# DC_Offset.net
KiCad netlist of a schematic drawn in EAGLE
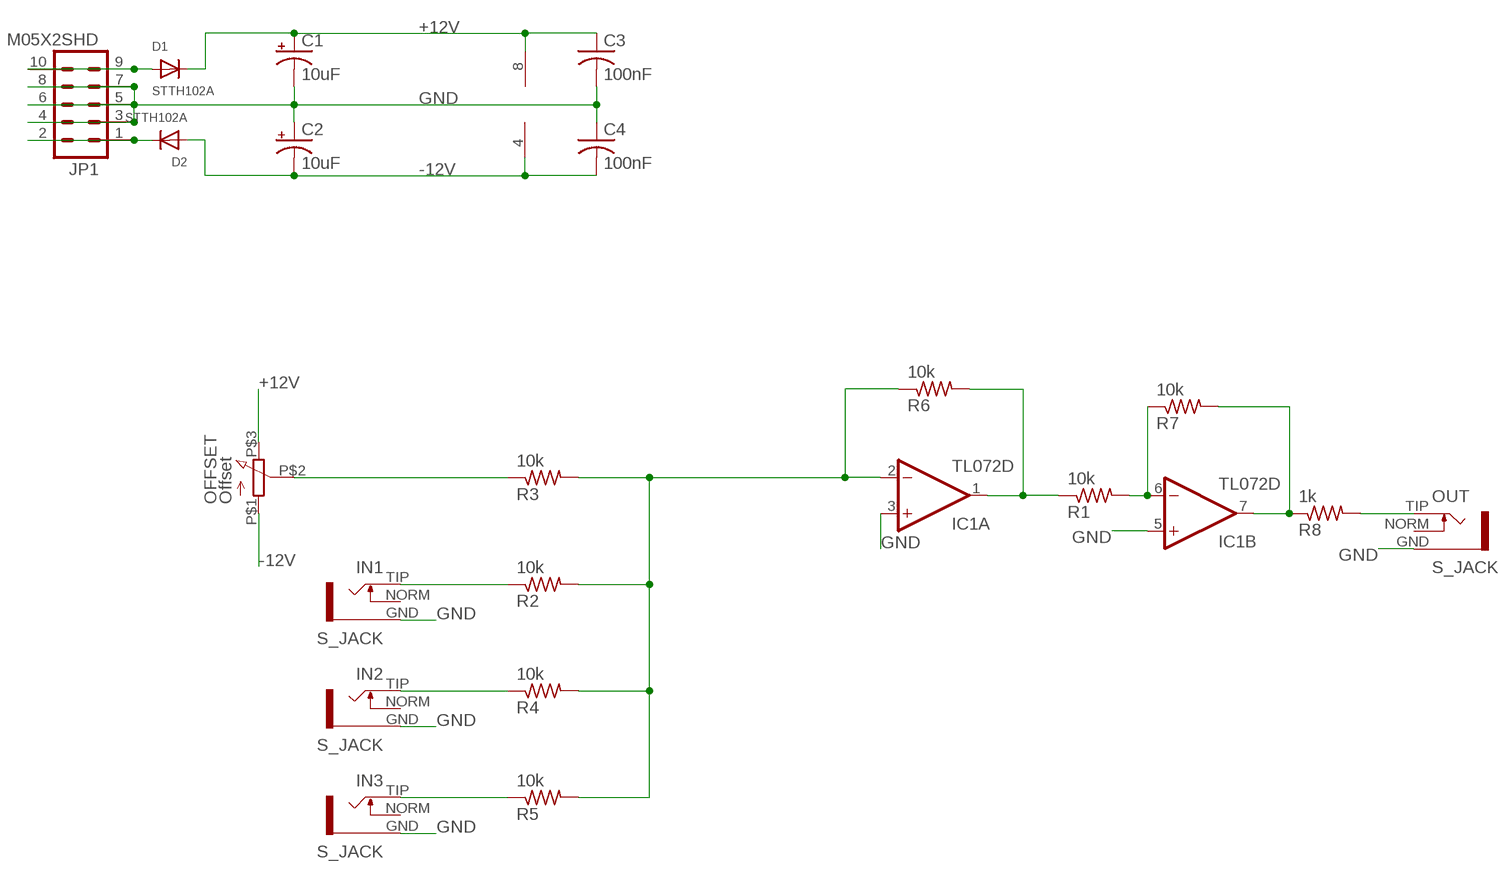
[diagram p0: schematic, sheet 1]

(export (version "E")
  (design (tool "Eeschema 10.0.6"))
  (components
    (comp (ref "C1")
      (value "10uF")
      (footprint "eagle-import:153CLV-0505")
      (libsource (lib "eagle-import") (part "CPOL-US153CLV-0505"))
    )
    (comp (ref "C2")
      (value "10uF")
      (footprint "eagle-import:153CLV-0505")
      (libsource (lib "eagle-import") (part "CPOL-US153CLV-0505"))
    )
    (comp (ref "C3")
      (value "100nF")
      (footprint "eagle-import:C0805")
      (libsource (lib "eagle-import") (part "C-USC0805"))
    )
    (comp (ref "C4")
      (value "100nF")
      (footprint "eagle-import:C0805")
      (libsource (lib "eagle-import") (part "C-USC0805"))
    )
    (comp (ref "D1")
      (value "STTH102A")
      (footprint "eagle-import:SMADIODE")
      (libsource (lib "eagle-import") (part "DIODESMA"))
    )
    (comp (ref "D2")
      (value "STTH102A")
      (footprint "eagle-import:SMADIODE")
      (libsource (lib "eagle-import") (part "DIODESMA"))
    )
    (comp (ref "IC1")
      (value "TL072D")
      (footprint "eagle-import:SO08")
      (libsource (lib "eagle-import") (part "TL072D"))
    )
    (comp (ref "IN1")
      (value "S_JACK")
      (footprint "eagle-import:S_JACK")
      (libsource (lib "eagle-import") (part "S_JACK"))
    )
    (comp (ref "IN2")
      (value "S_JACK")
      (footprint "eagle-import:S_JACK")
      (libsource (lib "eagle-import") (part "S_JACK"))
    )
    (comp (ref "IN3")
      (value "S_JACK")
      (footprint "eagle-import:S_JACK")
      (libsource (lib "eagle-import") (part "S_JACK"))
    )
    (comp (ref "JP1")
      (value "M05X2SHD")
      (footprint "eagle-import:2X5-SHROUDED")
      (libsource (lib "eagle-import") (part "M05X2SHD"))
    )
    (comp (ref "OFFSET")
      (value "Offset")
      (footprint "eagle-import:Q-POT")
      (libsource (lib "eagle-import") (part "Q-POT"))
    )
    (comp (ref "OUT")
      (value "S_JACK")
      (footprint "eagle-import:S_JACK")
      (libsource (lib "eagle-import") (part "S_JACK"))
    )
    (comp (ref "R1")
      (value "10k")
      (footprint "eagle-import:R0805")
      (libsource (lib "eagle-import") (part "R-US_R0805"))
    )
    (comp (ref "R2")
      (value "10k")
      (footprint "eagle-import:R0805")
      (libsource (lib "eagle-import") (part "R-US_R0805"))
    )
    (comp (ref "R3")
      (value "10k")
      (footprint "eagle-import:R0805")
      (libsource (lib "eagle-import") (part "R-US_R0805"))
    )
    (comp (ref "R4")
      (value "10k")
      (footprint "eagle-import:R0805")
      (libsource (lib "eagle-import") (part "R-US_R0805"))
    )
    (comp (ref "R5")
      (value "10k")
      (footprint "eagle-import:R0805")
      (libsource (lib "eagle-import") (part "R-US_R0805"))
    )
    (comp (ref "R6")
      (value "10k")
      (footprint "eagle-import:R0805")
      (libsource (lib "eagle-import") (part "R-US_R0805"))
    )
    (comp (ref "R7")
      (value "10k")
      (footprint "eagle-import:R0805")
      (libsource (lib "eagle-import") (part "R-US_R0805"))
    )
    (comp (ref "R8")
      (value "1k")
      (footprint "eagle-import:R0805")
      (libsource (lib "eagle-import") (part "R-US_R0805"))
    )
  )
  (nets
    (net (code "1") (name "/+12V") (class "Default")
      (node (ref "C1") (pin "+") (pinfunction "+_+") (pintype "passive"))
      (node (ref "C3") (pin "1") (pinfunction "1_1") (pintype "passive"))
      (node (ref "D1") (pin "C") (pinfunction "C_C") (pintype "passive"))
      (node (ref "IC1") (pin "8") (pinfunction "V+_8") (pintype "power_in"))
      (node (ref "OFFSET") (pin "P$3") (pinfunction "3_P$3") (pintype "passive"))
    )
    (net (code "2") (name "/-12V") (class "Default")
      (node (ref "C2") (pin "-") (pinfunction "-_-") (pintype "passive"))
      (node (ref "C4") (pin "2") (pinfunction "2_2") (pintype "passive"))
      (node (ref "D2") (pin "A") (pinfunction "A_A") (pintype "passive"))
      (node (ref "IC1") (pin "4") (pinfunction "V-_4") (pintype "power_in"))
      (node (ref "OFFSET") (pin "P$1") (pinfunction "1_P$1") (pintype "passive"))
    )
    (net (code "3") (name "/GND") (class "Default")
      (node (ref "C1") (pin "-") (pinfunction "-_-") (pintype "passive"))
      (node (ref "C2") (pin "+") (pinfunction "+_+") (pintype "passive"))
      (node (ref "C3") (pin "2") (pinfunction "2_2") (pintype "passive"))
      (node (ref "C4") (pin "1") (pinfunction "1_1") (pintype "passive"))
      (node (ref "IC1") (pin "3") (pinfunction "+IN_3") (pintype "input"))
      (node (ref "IC1") (pin "5") (pinfunction "+IN_5") (pintype "input"))
      (node (ref "IN1") (pin "GND") (pinfunction "GND_GND") (pintype "passive"))
      (node (ref "IN2") (pin "GND") (pinfunction "GND_GND") (pintype "passive"))
      (node (ref "IN3") (pin "GND") (pinfunction "GND_GND") (pintype "passive"))
      (node (ref "JP1") (pin "3") (pinfunction "3_3") (pintype "passive"))
      (node (ref "JP1") (pin "4") (pinfunction "4_4") (pintype "passive"))
      (node (ref "JP1") (pin "5") (pinfunction "5_5") (pintype "passive"))
      (node (ref "JP1") (pin "6") (pinfunction "6_6") (pintype "passive"))
      (node (ref "JP1") (pin "7") (pinfunction "7_7") (pintype "passive"))
      (node (ref "JP1") (pin "8") (pinfunction "8_8") (pintype "passive"))
      (node (ref "OUT") (pin "GND") (pinfunction "GND_GND") (pintype "passive"))
    )
    (net (code "4") (name "Net-(D1-PadA)") (class "Default")
      (node (ref "D1") (pin "A") (pinfunction "A_A") (pintype "passive"))
      (node (ref "JP1") (pin "10") (pinfunction "10_10") (pintype "passive"))
      (node (ref "JP1") (pin "9") (pinfunction "9_9") (pintype "passive"))
    )
    (net (code "5") (name "Net-(D2-PadC)") (class "Default")
      (node (ref "D2") (pin "C") (pinfunction "C_C") (pintype "passive"))
      (node (ref "JP1") (pin "1") (pinfunction "1_1") (pintype "passive"))
      (node (ref "JP1") (pin "2") (pinfunction "2_2") (pintype "passive"))
    )
    (net (code "6") (name "Net-(IC1A--IN)") (class "Default")
      (node (ref "IC1") (pin "2") (pinfunction "-IN_2") (pintype "input"))
      (node (ref "R2") (pin "2") (pinfunction "2_2") (pintype "passive"))
      (node (ref "R3") (pin "2") (pinfunction "2_2") (pintype "passive"))
      (node (ref "R4") (pin "2") (pinfunction "2_2") (pintype "passive"))
      (node (ref "R5") (pin "2") (pinfunction "2_2") (pintype "passive"))
      (node (ref "R6") (pin "1") (pinfunction "1_1") (pintype "passive"))
    )
    (net (code "7") (name "Net-(IC1A-OUT)") (class "Default")
      (node (ref "IC1") (pin "1") (pinfunction "OUT_1") (pintype "output"))
      (node (ref "R1") (pin "1") (pinfunction "1_1") (pintype "passive"))
      (node (ref "R6") (pin "2") (pinfunction "2_2") (pintype "passive"))
    )
    (net (code "8") (name "Net-(IC1B--IN)") (class "Default")
      (node (ref "IC1") (pin "6") (pinfunction "-IN_6") (pintype "input"))
      (node (ref "R1") (pin "2") (pinfunction "2_2") (pintype "passive"))
      (node (ref "R7") (pin "1") (pinfunction "1_1") (pintype "passive"))
    )
    (net (code "9") (name "Net-(IC1B-OUT)") (class "Default")
      (node (ref "IC1") (pin "7") (pinfunction "OUT_7") (pintype "output"))
      (node (ref "R7") (pin "2") (pinfunction "2_2") (pintype "passive"))
      (node (ref "R8") (pin "1") (pinfunction "1_1") (pintype "passive"))
    )
    (net (code "10") (name "Net-(IN1-PadTIP)") (class "Default")
      (node (ref "IN1") (pin "TIP") (pinfunction "TIP_TIP") (pintype "passive"))
      (node (ref "R2") (pin "1") (pinfunction "1_1") (pintype "passive"))
    )
    (net (code "11") (name "Net-(IN2-PadTIP)") (class "Default")
      (node (ref "IN2") (pin "TIP") (pinfunction "TIP_TIP") (pintype "passive"))
      (node (ref "R4") (pin "1") (pinfunction "1_1") (pintype "passive"))
    )
    (net (code "12") (name "Net-(IN3-PadTIP)") (class "Default")
      (node (ref "IN3") (pin "TIP") (pinfunction "TIP_TIP") (pintype "passive"))
      (node (ref "R5") (pin "1") (pinfunction "1_1") (pintype "passive"))
    )
    (net (code "13") (name "Net-(OFFSET-2)") (class "Default")
      (node (ref "OFFSET") (pin "P$2") (pinfunction "2_P$2") (pintype "passive"))
      (node (ref "R3") (pin "1") (pinfunction "1_1") (pintype "passive"))
    )
    (net (code "14") (name "Net-(OUT-PadTIP)") (class "Default")
      (node (ref "OUT") (pin "TIP") (pinfunction "TIP_TIP") (pintype "passive"))
      (node (ref "R8") (pin "2") (pinfunction "2_2") (pintype "passive"))
    )
    (net (code "15") (name "unconnected-(IN1-PadNORM)") (class "Default")
      (node (ref "IN1") (pin "NORM") (pinfunction "NORM_NORM") (pintype "passive"))
    )
    (net (code "16") (name "unconnected-(IN2-PadNORM)") (class "Default")
      (node (ref "IN2") (pin "NORM") (pinfunction "NORM_NORM") (pintype "passive"))
    )
    (net (code "17") (name "unconnected-(IN3-PadNORM)") (class "Default")
      (node (ref "IN3") (pin "NORM") (pinfunction "NORM_NORM") (pintype "passive"))
    )
    (net (code "18") (name "unconnected-(OUT-PadNORM)") (class "Default")
      (node (ref "OUT") (pin "NORM") (pinfunction "NORM_NORM") (pintype "passive"))
    )
  )
)
